# p8_led_matrix.net
KiCad netlist of a schematic drawn in Altium Designer
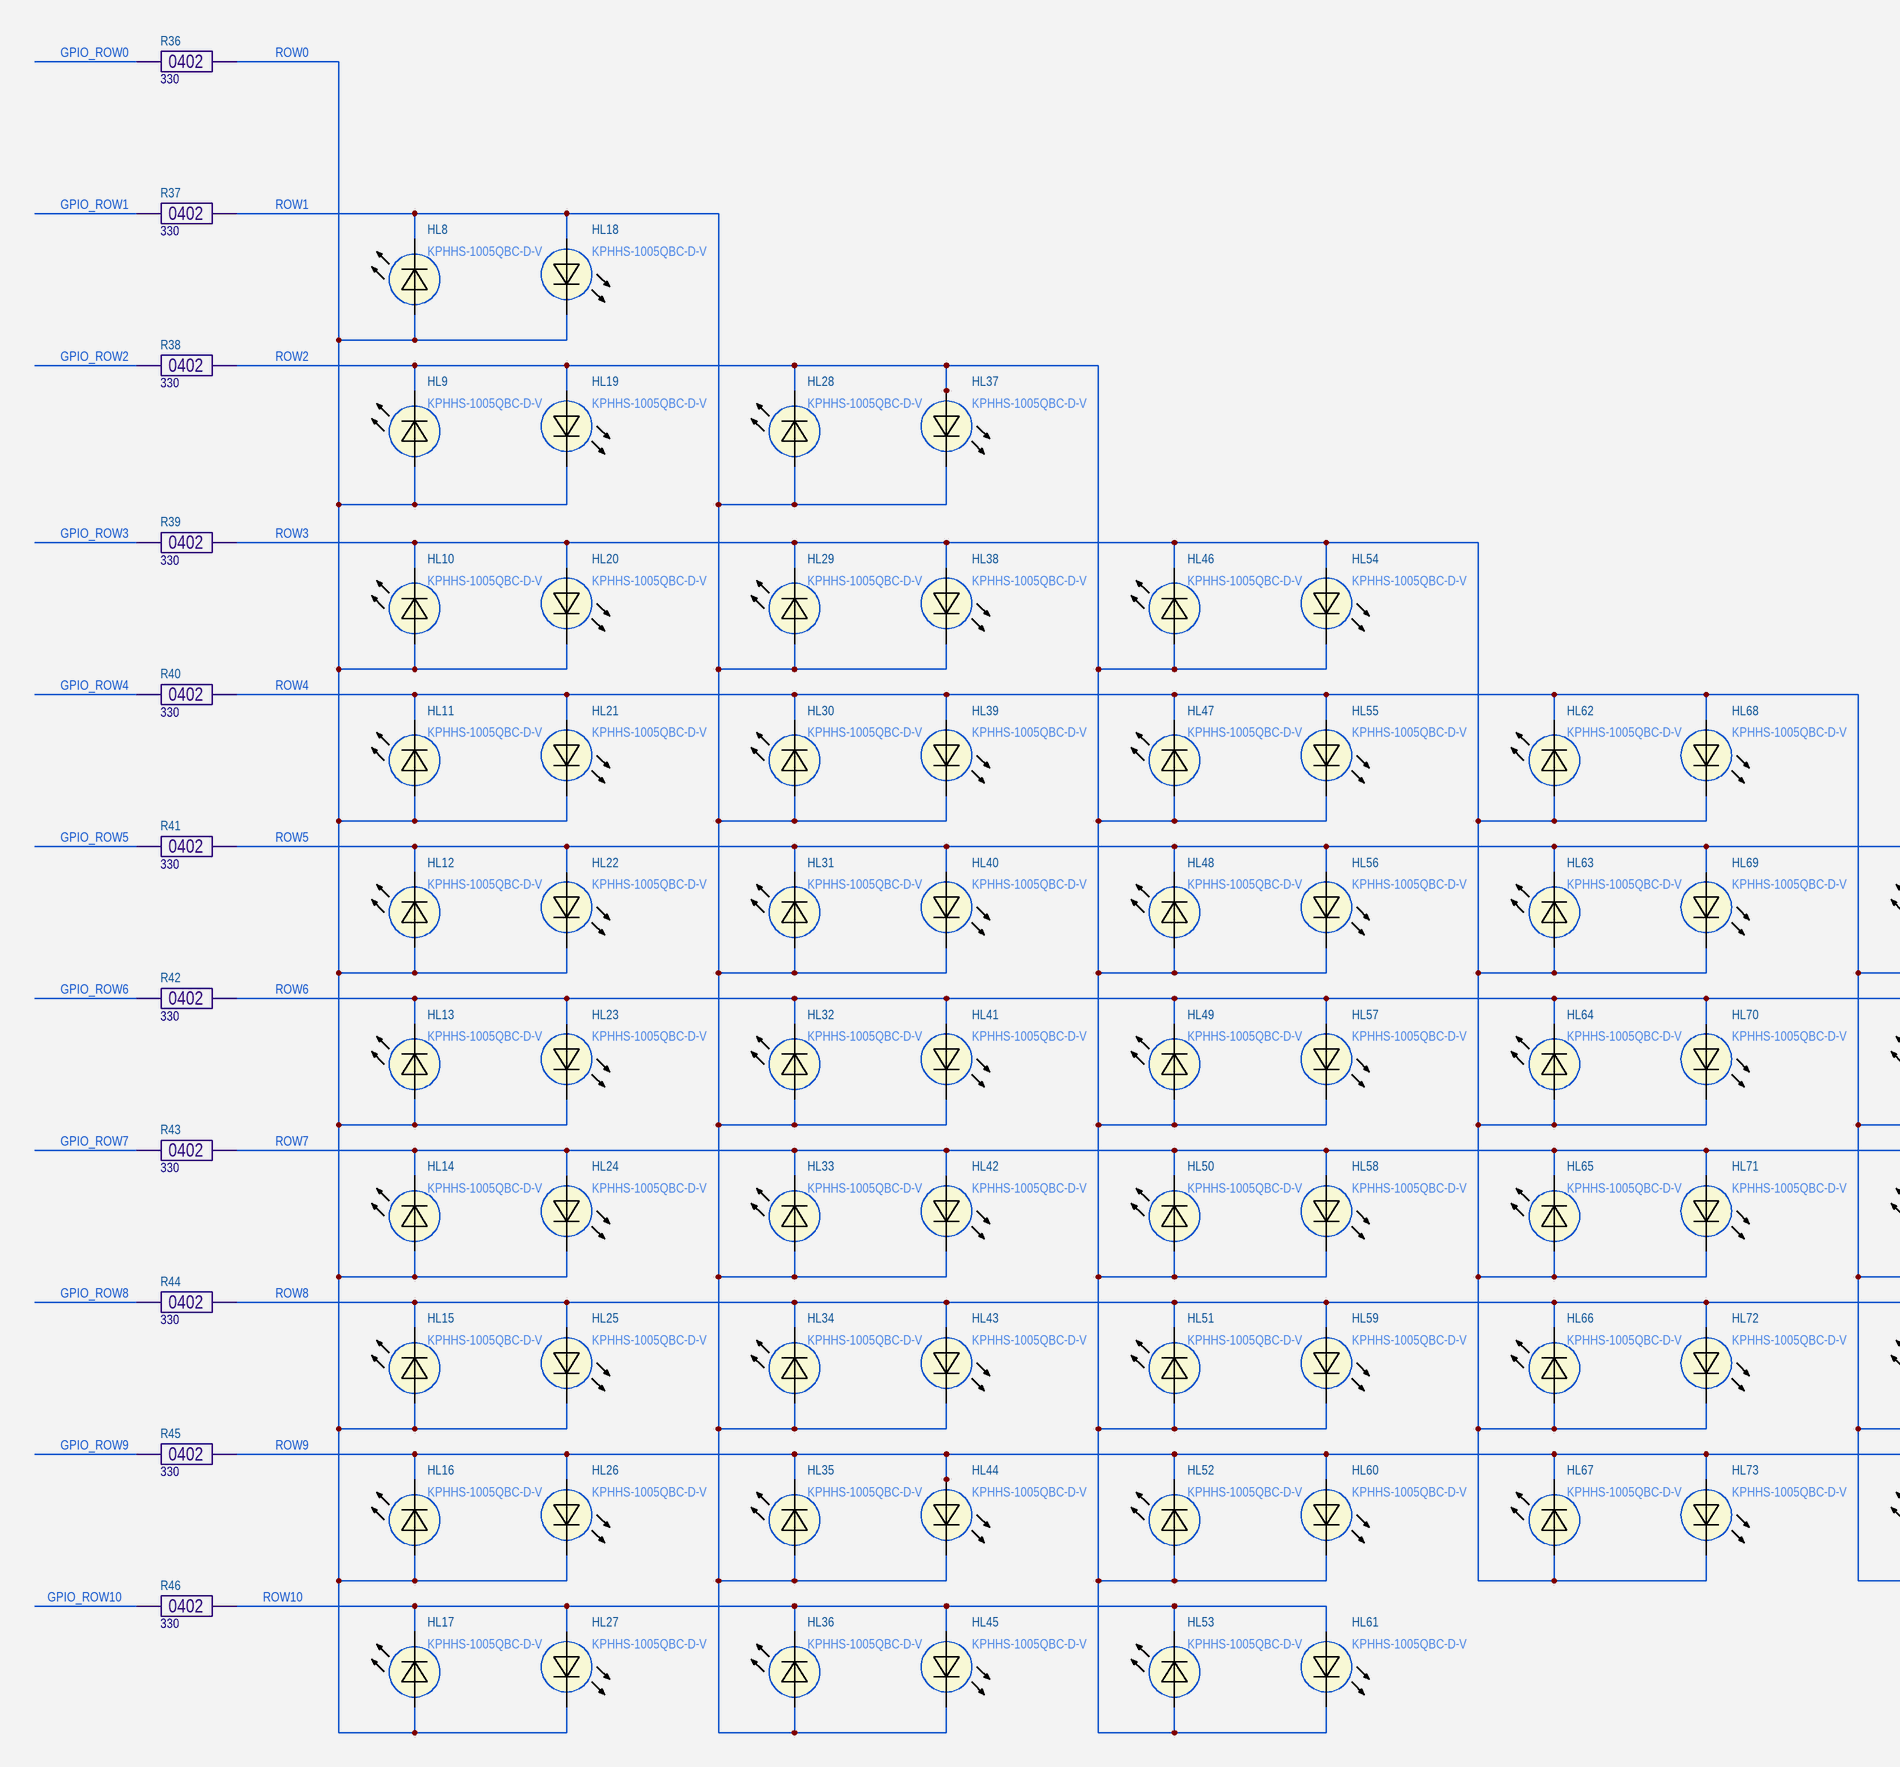
[diagram p0: p8_led_matrix.SchDoc, left]
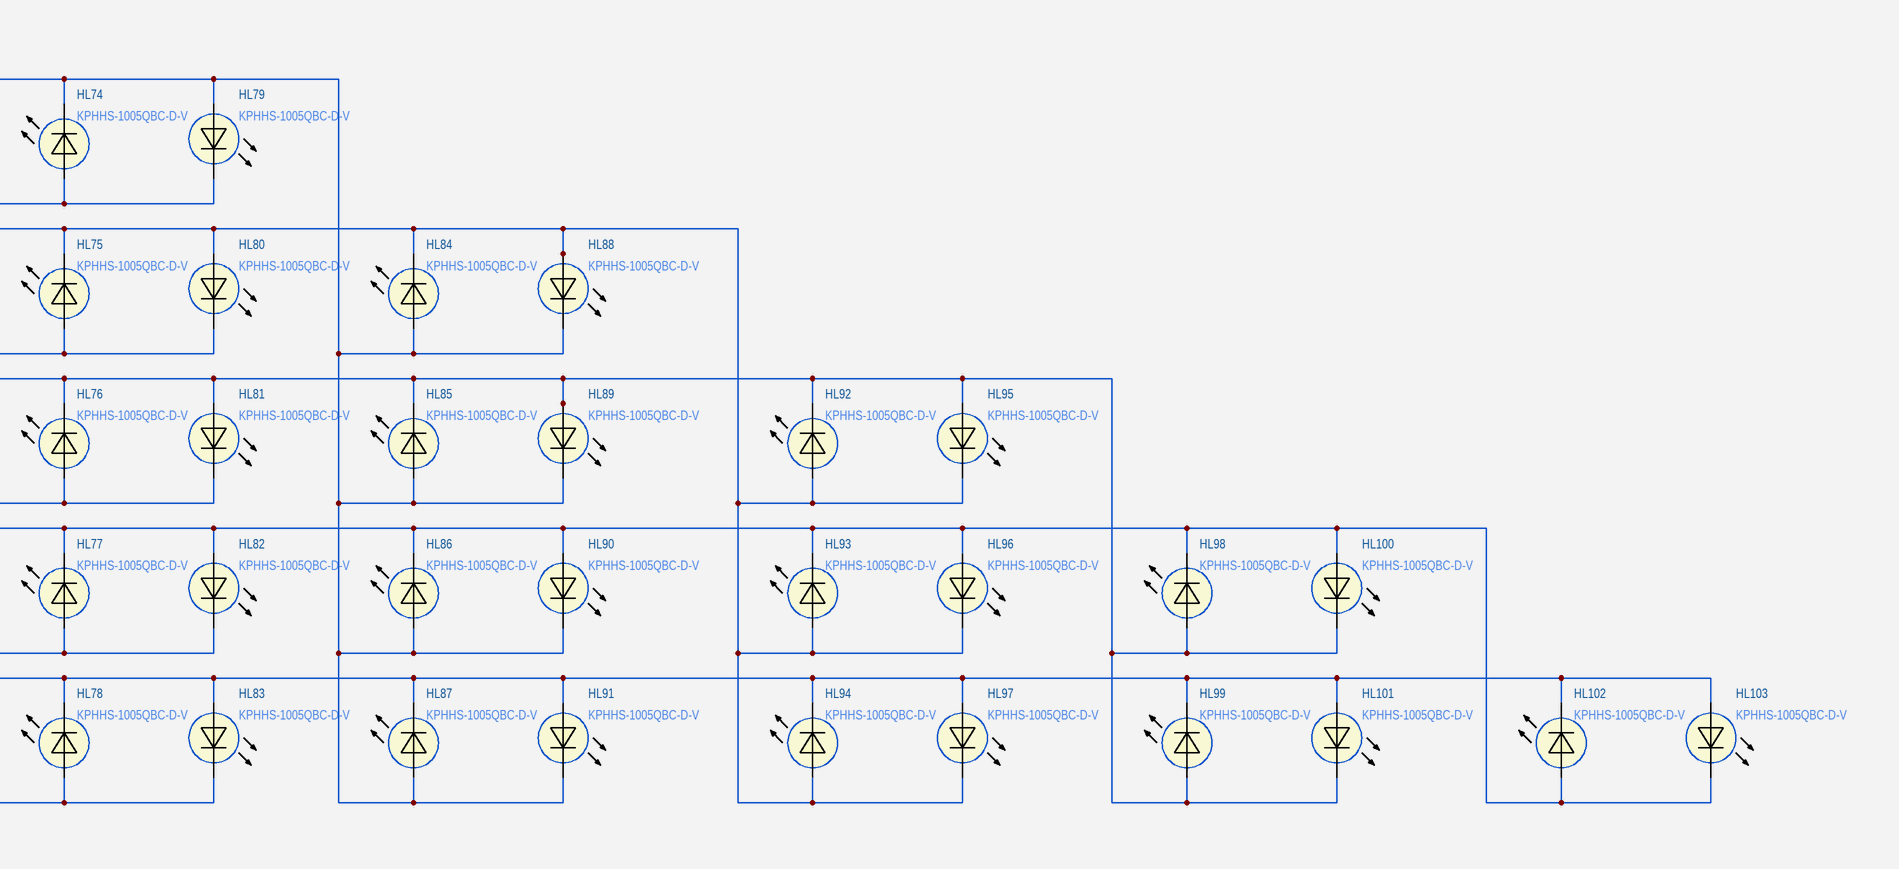
[diagram p1: p8_led_matrix.SchDoc, right]

(export (version "E")
  (design (tool "Eeschema 10.0.6"))
  (components
    (comp (ref "HL8")
      (value "KPHHS-1005QBC-D-V")
      (footprint "PcbLib_Others:LED0402B")
      (description "Blue led (package case 0402)")
      (fields (field (name "MANUFACTURER") "Kingbright Company LLC."))
      (libsource (lib "Schlib_Kingbright") (part "KPHHS-1005QBC-D-V"))
    )
    (comp (ref "HL9")
      (value "KPHHS-1005QBC-D-V")
      (footprint "PcbLib_Others:LED0402B")
      (description "Blue led (package case 0402)")
      (fields (field (name "MANUFACTURER") "Kingbright Company LLC."))
      (libsource (lib "Schlib_Kingbright") (part "KPHHS-1005QBC-D-V"))
    )
    (comp (ref "HL10")
      (value "KPHHS-1005QBC-D-V")
      (footprint "PcbLib_Others:LED0402B")
      (description "Blue led (package case 0402)")
      (fields (field (name "MANUFACTURER") "Kingbright Company LLC."))
      (libsource (lib "Schlib_Kingbright") (part "KPHHS-1005QBC-D-V"))
    )
    (comp (ref "HL11")
      (value "KPHHS-1005QBC-D-V")
      (footprint "PcbLib_Others:LED0402B")
      (description "Blue led (package case 0402)")
      (fields (field (name "MANUFACTURER") "Kingbright Company LLC."))
      (libsource (lib "Schlib_Kingbright") (part "KPHHS-1005QBC-D-V"))
    )
    (comp (ref "HL12")
      (value "KPHHS-1005QBC-D-V")
      (footprint "PcbLib_Others:LED0402B")
      (description "Blue led (package case 0402)")
      (fields (field (name "MANUFACTURER") "Kingbright Company LLC."))
      (libsource (lib "Schlib_Kingbright") (part "KPHHS-1005QBC-D-V"))
    )
    (comp (ref "HL13")
      (value "KPHHS-1005QBC-D-V")
      (footprint "PcbLib_Others:LED0402B")
      (description "Blue led (package case 0402)")
      (fields (field (name "MANUFACTURER") "Kingbright Company LLC."))
      (libsource (lib "Schlib_Kingbright") (part "KPHHS-1005QBC-D-V"))
    )
    (comp (ref "HL14")
      (value "KPHHS-1005QBC-D-V")
      (footprint "PcbLib_Others:LED0402B")
      (description "Blue led (package case 0402)")
      (fields (field (name "MANUFACTURER") "Kingbright Company LLC."))
      (libsource (lib "Schlib_Kingbright") (part "KPHHS-1005QBC-D-V"))
    )
    (comp (ref "HL15")
      (value "KPHHS-1005QBC-D-V")
      (footprint "PcbLib_Others:LED0402B")
      (description "Blue led (package case 0402)")
      (fields (field (name "MANUFACTURER") "Kingbright Company LLC."))
      (libsource (lib "Schlib_Kingbright") (part "KPHHS-1005QBC-D-V"))
    )
    (comp (ref "HL16")
      (value "KPHHS-1005QBC-D-V")
      (footprint "PcbLib_Others:LED0402B")
      (description "Blue led (package case 0402)")
      (fields (field (name "MANUFACTURER") "Kingbright Company LLC."))
      (libsource (lib "Schlib_Kingbright") (part "KPHHS-1005QBC-D-V"))
    )
    (comp (ref "HL17")
      (value "KPHHS-1005QBC-D-V")
      (footprint "PcbLib_Others:LED0402B")
      (description "Blue led (package case 0402)")
      (fields (field (name "MANUFACTURER") "Kingbright Company LLC."))
      (libsource (lib "Schlib_Kingbright") (part "KPHHS-1005QBC-D-V"))
    )
    (comp (ref "HL18")
      (value "KPHHS-1005QBC-D-V")
      (footprint "PcbLib_Others:LED0402B")
      (description "Blue led (package case 0402)")
      (fields (field (name "MANUFACTURER") "Kingbright Company LLC."))
      (libsource (lib "Schlib_Kingbright") (part "KPHHS-1005QBC-D-V"))
    )
    (comp (ref "HL19")
      (value "KPHHS-1005QBC-D-V")
      (footprint "PcbLib_Others:LED0402B")
      (description "Blue led (package case 0402)")
      (fields (field (name "MANUFACTURER") "Kingbright Company LLC."))
      (libsource (lib "Schlib_Kingbright") (part "KPHHS-1005QBC-D-V"))
    )
    (comp (ref "HL20")
      (value "KPHHS-1005QBC-D-V")
      (footprint "PcbLib_Others:LED0402B")
      (description "Blue led (package case 0402)")
      (fields (field (name "MANUFACTURER") "Kingbright Company LLC."))
      (libsource (lib "Schlib_Kingbright") (part "KPHHS-1005QBC-D-V"))
    )
    (comp (ref "HL21")
      (value "KPHHS-1005QBC-D-V")
      (footprint "PcbLib_Others:LED0402B")
      (description "Blue led (package case 0402)")
      (fields (field (name "MANUFACTURER") "Kingbright Company LLC."))
      (libsource (lib "Schlib_Kingbright") (part "KPHHS-1005QBC-D-V"))
    )
    (comp (ref "HL22")
      (value "KPHHS-1005QBC-D-V")
      (footprint "PcbLib_Others:LED0402B")
      (description "Blue led (package case 0402)")
      (fields (field (name "MANUFACTURER") "Kingbright Company LLC."))
      (libsource (lib "Schlib_Kingbright") (part "KPHHS-1005QBC-D-V"))
    )
    (comp (ref "HL23")
      (value "KPHHS-1005QBC-D-V")
      (footprint "PcbLib_Others:LED0402B")
      (description "Blue led (package case 0402)")
      (fields (field (name "MANUFACTURER") "Kingbright Company LLC."))
      (libsource (lib "Schlib_Kingbright") (part "KPHHS-1005QBC-D-V"))
    )
    (comp (ref "HL24")
      (value "KPHHS-1005QBC-D-V")
      (footprint "PcbLib_Others:LED0402B")
      (description "Blue led (package case 0402)")
      (fields (field (name "MANUFACTURER") "Kingbright Company LLC."))
      (libsource (lib "Schlib_Kingbright") (part "KPHHS-1005QBC-D-V"))
    )
    (comp (ref "HL25")
      (value "KPHHS-1005QBC-D-V")
      (footprint "PcbLib_Others:LED0402B")
      (description "Blue led (package case 0402)")
      (fields (field (name "MANUFACTURER") "Kingbright Company LLC."))
      (libsource (lib "Schlib_Kingbright") (part "KPHHS-1005QBC-D-V"))
    )
    (comp (ref "HL26")
      (value "KPHHS-1005QBC-D-V")
      (footprint "PcbLib_Others:LED0402B")
      (description "Blue led (package case 0402)")
      (fields (field (name "MANUFACTURER") "Kingbright Company LLC."))
      (libsource (lib "Schlib_Kingbright") (part "KPHHS-1005QBC-D-V"))
    )
    (comp (ref "HL27")
      (value "KPHHS-1005QBC-D-V")
      (footprint "PcbLib_Others:LED0402B")
      (description "Blue led (package case 0402)")
      (fields (field (name "MANUFACTURER") "Kingbright Company LLC."))
      (libsource (lib "Schlib_Kingbright") (part "KPHHS-1005QBC-D-V"))
    )
    (comp (ref "HL28")
      (value "KPHHS-1005QBC-D-V")
      (footprint "PcbLib_Others:LED0402B")
      (description "Blue led (package case 0402)")
      (fields (field (name "MANUFACTURER") "Kingbright Company LLC."))
      (libsource (lib "Schlib_Kingbright") (part "KPHHS-1005QBC-D-V"))
    )
    (comp (ref "HL29")
      (value "KPHHS-1005QBC-D-V")
      (footprint "PcbLib_Others:LED0402B")
      (description "Blue led (package case 0402)")
      (fields (field (name "MANUFACTURER") "Kingbright Company LLC."))
      (libsource (lib "Schlib_Kingbright") (part "KPHHS-1005QBC-D-V"))
    )
    (comp (ref "HL30")
      (value "KPHHS-1005QBC-D-V")
      (footprint "PcbLib_Others:LED0402B")
      (description "Blue led (package case 0402)")
      (fields (field (name "MANUFACTURER") "Kingbright Company LLC."))
      (libsource (lib "Schlib_Kingbright") (part "KPHHS-1005QBC-D-V"))
    )
    (comp (ref "HL31")
      (value "KPHHS-1005QBC-D-V")
      (footprint "PcbLib_Others:LED0402B")
      (description "Blue led (package case 0402)")
      (fields (field (name "MANUFACTURER") "Kingbright Company LLC."))
      (libsource (lib "Schlib_Kingbright") (part "KPHHS-1005QBC-D-V"))
    )
    (comp (ref "HL32")
      (value "KPHHS-1005QBC-D-V")
      (footprint "PcbLib_Others:LED0402B")
      (description "Blue led (package case 0402)")
      (fields (field (name "MANUFACTURER") "Kingbright Company LLC."))
      (libsource (lib "Schlib_Kingbright") (part "KPHHS-1005QBC-D-V"))
    )
    (comp (ref "HL33")
      (value "KPHHS-1005QBC-D-V")
      (footprint "PcbLib_Others:LED0402B")
      (description "Blue led (package case 0402)")
      (fields (field (name "MANUFACTURER") "Kingbright Company LLC."))
      (libsource (lib "Schlib_Kingbright") (part "KPHHS-1005QBC-D-V"))
    )
    (comp (ref "HL34")
      (value "KPHHS-1005QBC-D-V")
      (footprint "PcbLib_Others:LED0402B")
      (description "Blue led (package case 0402)")
      (fields (field (name "MANUFACTURER") "Kingbright Company LLC."))
      (libsource (lib "Schlib_Kingbright") (part "KPHHS-1005QBC-D-V"))
    )
    (comp (ref "HL35")
      (value "KPHHS-1005QBC-D-V")
      (footprint "PcbLib_Others:LED0402B")
      (description "Blue led (package case 0402)")
      (fields (field (name "MANUFACTURER") "Kingbright Company LLC."))
      (libsource (lib "Schlib_Kingbright") (part "KPHHS-1005QBC-D-V"))
    )
    (comp (ref "HL36")
      (value "KPHHS-1005QBC-D-V")
      (footprint "PcbLib_Others:LED0402B")
      (description "Blue led (package case 0402)")
      (fields (field (name "MANUFACTURER") "Kingbright Company LLC."))
      (libsource (lib "Schlib_Kingbright") (part "KPHHS-1005QBC-D-V"))
    )
    (comp (ref "HL37")
      (value "KPHHS-1005QBC-D-V")
      (footprint "PcbLib_Others:LED0402B")
      (description "Blue led (package case 0402)")
      (fields (field (name "MANUFACTURER") "Kingbright Company LLC."))
      (libsource (lib "Schlib_Kingbright") (part "KPHHS-1005QBC-D-V"))
    )
    (comp (ref "HL38")
      (value "KPHHS-1005QBC-D-V")
      (footprint "PcbLib_Others:LED0402B")
      (description "Blue led (package case 0402)")
      (fields (field (name "MANUFACTURER") "Kingbright Company LLC."))
      (libsource (lib "Schlib_Kingbright") (part "KPHHS-1005QBC-D-V"))
    )
    (comp (ref "HL39")
      (value "KPHHS-1005QBC-D-V")
      (footprint "PcbLib_Others:LED0402B")
      (description "Blue led (package case 0402)")
      (fields (field (name "MANUFACTURER") "Kingbright Company LLC."))
      (libsource (lib "Schlib_Kingbright") (part "KPHHS-1005QBC-D-V"))
    )
    (comp (ref "HL40")
      (value "KPHHS-1005QBC-D-V")
      (footprint "PcbLib_Others:LED0402B")
      (description "Blue led (package case 0402)")
      (fields (field (name "MANUFACTURER") "Kingbright Company LLC."))
      (libsource (lib "Schlib_Kingbright") (part "KPHHS-1005QBC-D-V"))
    )
    (comp (ref "HL41")
      (value "KPHHS-1005QBC-D-V")
      (footprint "PcbLib_Others:LED0402B")
      (description "Blue led (package case 0402)")
      (fields (field (name "MANUFACTURER") "Kingbright Company LLC."))
      (libsource (lib "Schlib_Kingbright") (part "KPHHS-1005QBC-D-V"))
    )
    (comp (ref "HL42")
      (value "KPHHS-1005QBC-D-V")
      (footprint "PcbLib_Others:LED0402B")
      (description "Blue led (package case 0402)")
      (fields (field (name "MANUFACTURER") "Kingbright Company LLC."))
      (libsource (lib "Schlib_Kingbright") (part "KPHHS-1005QBC-D-V"))
    )
    (comp (ref "HL43")
      (value "KPHHS-1005QBC-D-V")
      (footprint "PcbLib_Others:LED0402B")
      (description "Blue led (package case 0402)")
      (fields (field (name "MANUFACTURER") "Kingbright Company LLC."))
      (libsource (lib "Schlib_Kingbright") (part "KPHHS-1005QBC-D-V"))
    )
    (comp (ref "HL44")
      (value "KPHHS-1005QBC-D-V")
      (footprint "PcbLib_Others:LED0402B")
      (description "Blue led (package case 0402)")
      (fields (field (name "MANUFACTURER") "Kingbright Company LLC."))
      (libsource (lib "Schlib_Kingbright") (part "KPHHS-1005QBC-D-V"))
    )
    (comp (ref "HL45")
      (value "KPHHS-1005QBC-D-V")
      (footprint "PcbLib_Others:LED0402B")
      (description "Blue led (package case 0402)")
      (fields (field (name "MANUFACTURER") "Kingbright Company LLC."))
      (libsource (lib "Schlib_Kingbright") (part "KPHHS-1005QBC-D-V"))
    )
    (comp (ref "HL46")
      (value "KPHHS-1005QBC-D-V")
      (footprint "PcbLib_Others:LED0402B")
      (description "Blue led (package case 0402)")
      (fields (field (name "MANUFACTURER") "Kingbright Company LLC."))
      (libsource (lib "Schlib_Kingbright") (part "KPHHS-1005QBC-D-V"))
    )
    (comp (ref "HL47")
      (value "KPHHS-1005QBC-D-V")
      (footprint "PcbLib_Others:LED0402B")
      (description "Blue led (package case 0402)")
      (fields (field (name "MANUFACTURER") "Kingbright Company LLC."))
      (libsource (lib "Schlib_Kingbright") (part "KPHHS-1005QBC-D-V"))
    )
    (comp (ref "HL48")
      (value "KPHHS-1005QBC-D-V")
      (footprint "PcbLib_Others:LED0402B")
      (description "Blue led (package case 0402)")
      (fields (field (name "MANUFACTURER") "Kingbright Company LLC."))
      (libsource (lib "Schlib_Kingbright") (part "KPHHS-1005QBC-D-V"))
    )
    (comp (ref "HL49")
      (value "KPHHS-1005QBC-D-V")
      (footprint "PcbLib_Others:LED0402B")
      (description "Blue led (package case 0402)")
      (fields (field (name "MANUFACTURER") "Kingbright Company LLC."))
      (libsource (lib "Schlib_Kingbright") (part "KPHHS-1005QBC-D-V"))
    )
    (comp (ref "HL50")
      (value "KPHHS-1005QBC-D-V")
      (footprint "PcbLib_Others:LED0402B")
      (description "Blue led (package case 0402)")
      (fields (field (name "MANUFACTURER") "Kingbright Company LLC."))
      (libsource (lib "Schlib_Kingbright") (part "KPHHS-1005QBC-D-V"))
    )
    (comp (ref "HL51")
      (value "KPHHS-1005QBC-D-V")
      (footprint "PcbLib_Others:LED0402B")
      (description "Blue led (package case 0402)")
      (fields (field (name "MANUFACTURER") "Kingbright Company LLC."))
      (libsource (lib "Schlib_Kingbright") (part "KPHHS-1005QBC-D-V"))
    )
    (comp (ref "HL52")
      (value "KPHHS-1005QBC-D-V")
      (footprint "PcbLib_Others:LED0402B")
      (description "Blue led (package case 0402)")
      (fields (field (name "MANUFACTURER") "Kingbright Company LLC."))
      (libsource (lib "Schlib_Kingbright") (part "KPHHS-1005QBC-D-V"))
    )
    (comp (ref "HL53")
      (value "KPHHS-1005QBC-D-V")
      (footprint "PcbLib_Others:LED0402B")
      (description "Blue led (package case 0402)")
      (fields (field (name "MANUFACTURER") "Kingbright Company LLC."))
      (libsource (lib "Schlib_Kingbright") (part "KPHHS-1005QBC-D-V"))
    )
    (comp (ref "HL54")
      (value "KPHHS-1005QBC-D-V")
      (footprint "PcbLib_Others:LED0402B")
      (description "Blue led (package case 0402)")
      (fields (field (name "MANUFACTURER") "Kingbright Company LLC."))
      (libsource (lib "Schlib_Kingbright") (part "KPHHS-1005QBC-D-V"))
    )
    (comp (ref "HL55")
      (value "KPHHS-1005QBC-D-V")
      (footprint "PcbLib_Others:LED0402B")
      (description "Blue led (package case 0402)")
      (fields (field (name "MANUFACTURER") "Kingbright Company LLC."))
      (libsource (lib "Schlib_Kingbright") (part "KPHHS-1005QBC-D-V"))
    )
    (comp (ref "HL56")
      (value "KPHHS-1005QBC-D-V")
      (footprint "PcbLib_Others:LED0402B")
      (description "Blue led (package case 0402)")
      (fields (field (name "MANUFACTURER") "Kingbright Company LLC."))
      (libsource (lib "Schlib_Kingbright") (part "KPHHS-1005QBC-D-V"))
    )
    (comp (ref "HL57")
      (value "KPHHS-1005QBC-D-V")
      (footprint "PcbLib_Others:LED0402B")
      (description "Blue led (package case 0402)")
      (fields (field (name "MANUFACTURER") "Kingbright Company LLC."))
      (libsource (lib "Schlib_Kingbright") (part "KPHHS-1005QBC-D-V"))
    )
    (comp (ref "HL58")
      (value "KPHHS-1005QBC-D-V")
      (footprint "PcbLib_Others:LED0402B")
      (description "Blue led (package case 0402)")
      (fields (field (name "MANUFACTURER") "Kingbright Company LLC."))
      (libsource (lib "Schlib_Kingbright") (part "KPHHS-1005QBC-D-V"))
    )
    (comp (ref "HL59")
      (value "KPHHS-1005QBC-D-V")
      (footprint "PcbLib_Others:LED0402B")
      (description "Blue led (package case 0402)")
      (fields (field (name "MANUFACTURER") "Kingbright Company LLC."))
      (libsource (lib "Schlib_Kingbright") (part "KPHHS-1005QBC-D-V"))
    )
    (comp (ref "HL60")
      (value "KPHHS-1005QBC-D-V")
      (footprint "PcbLib_Others:LED0402B")
      (description "Blue led (package case 0402)")
      (fields (field (name "MANUFACTURER") "Kingbright Company LLC."))
      (libsource (lib "Schlib_Kingbright") (part "KPHHS-1005QBC-D-V"))
    )
    (comp (ref "HL61")
      (value "KPHHS-1005QBC-D-V")
      (footprint "PcbLib_Others:LED0402B")
      (description "Blue led (package case 0402)")
      (fields (field (name "MANUFACTURER") "Kingbright Company LLC."))
      (libsource (lib "Schlib_Kingbright") (part "KPHHS-1005QBC-D-V"))
    )
    (comp (ref "HL62")
      (value "KPHHS-1005QBC-D-V")
      (footprint "PcbLib_Others:LED0402B")
      (description "Blue led (package case 0402)")
      (fields (field (name "MANUFACTURER") "Kingbright Company LLC."))
      (libsource (lib "Schlib_Kingbright") (part "KPHHS-1005QBC-D-V"))
    )
    (comp (ref "HL63")
      (value "KPHHS-1005QBC-D-V")
      (footprint "PcbLib_Others:LED0402B")
      (description "Blue led (package case 0402)")
      (fields (field (name "MANUFACTURER") "Kingbright Company LLC."))
      (libsource (lib "Schlib_Kingbright") (part "KPHHS-1005QBC-D-V"))
    )
    (comp (ref "HL64")
      (value "KPHHS-1005QBC-D-V")
      (footprint "PcbLib_Others:LED0402B")
      (description "Blue led (package case 0402)")
      (fields (field (name "MANUFACTURER") "Kingbright Company LLC."))
      (libsource (lib "Schlib_Kingbright") (part "KPHHS-1005QBC-D-V"))
    )
    (comp (ref "HL65")
      (value "KPHHS-1005QBC-D-V")
      (footprint "PcbLib_Others:LED0402B")
      (description "Blue led (package case 0402)")
      (fields (field (name "MANUFACTURER") "Kingbright Company LLC."))
      (libsource (lib "Schlib_Kingbright") (part "KPHHS-1005QBC-D-V"))
    )
    (comp (ref "HL66")
      (value "KPHHS-1005QBC-D-V")
      (footprint "PcbLib_Others:LED0402B")
      (description "Blue led (package case 0402)")
      (fields (field (name "MANUFACTURER") "Kingbright Company LLC."))
      (libsource (lib "Schlib_Kingbright") (part "KPHHS-1005QBC-D-V"))
    )
    (comp (ref "HL67")
      (value "KPHHS-1005QBC-D-V")
      (footprint "PcbLib_Others:LED0402B")
      (description "Blue led (package case 0402)")
      (fields (field (name "MANUFACTURER") "Kingbright Company LLC."))
      (libsource (lib "Schlib_Kingbright") (part "KPHHS-1005QBC-D-V"))
    )
    (comp (ref "HL68")
      (value "KPHHS-1005QBC-D-V")
      (footprint "PcbLib_Others:LED0402B")
      (description "Blue led (package case 0402)")
      (fields (field (name "MANUFACTURER") "Kingbright Company LLC."))
      (libsource (lib "Schlib_Kingbright") (part "KPHHS-1005QBC-D-V"))
    )
    (comp (ref "HL69")
      (value "KPHHS-1005QBC-D-V")
      (footprint "PcbLib_Others:LED0402B")
      (description "Blue led (package case 0402)")
      (fields (field (name "MANUFACTURER") "Kingbright Company LLC."))
      (libsource (lib "Schlib_Kingbright") (part "KPHHS-1005QBC-D-V"))
    )
    (comp (ref "HL70")
      (value "KPHHS-1005QBC-D-V")
      (footprint "PcbLib_Others:LED0402B")
      (description "Blue led (package case 0402)")
      (fields (field (name "MANUFACTURER") "Kingbright Company LLC."))
      (libsource (lib "Schlib_Kingbright") (part "KPHHS-1005QBC-D-V"))
    )
    (comp (ref "HL71")
      (value "KPHHS-1005QBC-D-V")
      (footprint "PcbLib_Others:LED0402B")
      (description "Blue led (package case 0402)")
      (fields (field (name "MANUFACTURER") "Kingbright Company LLC."))
      (libsource (lib "Schlib_Kingbright") (part "KPHHS-1005QBC-D-V"))
    )
    (comp (ref "HL72")
      (value "KPHHS-1005QBC-D-V")
      (footprint "PcbLib_Others:LED0402B")
      (description "Blue led (package case 0402)")
      (fields (field (name "MANUFACTURER") "Kingbright Company LLC."))
      (libsource (lib "Schlib_Kingbright") (part "KPHHS-1005QBC-D-V"))
    )
    (comp (ref "HL73")
      (value "KPHHS-1005QBC-D-V")
      (footprint "PcbLib_Others:LED0402B")
      (description "Blue led (package case 0402)")
      (fields (field (name "MANUFACTURER") "Kingbright Company LLC."))
      (libsource (lib "Schlib_Kingbright") (part "KPHHS-1005QBC-D-V"))
    )
    (comp (ref "HL74")
      (value "KPHHS-1005QBC-D-V")
      (footprint "PcbLib_Others:LED0402B")
      (description "Blue led (package case 0402)")
      (fields (field (name "MANUFACTURER") "Kingbright Company LLC."))
      (libsource (lib "Schlib_Kingbright") (part "KPHHS-1005QBC-D-V"))
    )
    (comp (ref "HL75")
      (value "KPHHS-1005QBC-D-V")
      (footprint "PcbLib_Others:LED0402B")
      (description "Blue led (package case 0402)")
      (fields (field (name "MANUFACTURER") "Kingbright Company LLC."))
      (libsource (lib "Schlib_Kingbright") (part "KPHHS-1005QBC-D-V"))
    )
    (comp (ref "HL76")
      (value "KPHHS-1005QBC-D-V")
      (footprint "PcbLib_Others:LED0402B")
      (description "Blue led (package case 0402)")
      (fields (field (name "MANUFACTURER") "Kingbright Company LLC."))
      (libsource (lib "Schlib_Kingbright") (part "KPHHS-1005QBC-D-V"))
    )
    (comp (ref "HL77")
      (value "KPHHS-1005QBC-D-V")
      (footprint "PcbLib_Others:LED0402B")
      (description "Blue led (package case 0402)")
      (fields (field (name "MANUFACTURER") "Kingbright Company LLC."))
      (libsource (lib "Schlib_Kingbright") (part "KPHHS-1005QBC-D-V"))
    )
    (comp (ref "HL78")
      (value "KPHHS-1005QBC-D-V")
      (footprint "PcbLib_Others:LED0402B")
      (description "Blue led (package case 0402)")
      (fields (field (name "MANUFACTURER") "Kingbright Company LLC."))
      (libsource (lib "Schlib_Kingbright") (part "KPHHS-1005QBC-D-V"))
    )
    (comp (ref "HL79")
      (value "KPHHS-1005QBC-D-V")
      (footprint "PcbLib_Others:LED0402B")
      (description "Blue led (package case 0402)")
      (fields (field (name "MANUFACTURER") "Kingbright Company LLC."))
      (libsource (lib "Schlib_Kingbright") (part "KPHHS-1005QBC-D-V"))
    )
    (comp (ref "HL80")
      (value "KPHHS-1005QBC-D-V")
      (footprint "PcbLib_Others:LED0402B")
      (description "Blue led (package case 0402)")
      (fields (field (name "MANUFACTURER") "Kingbright Company LLC."))
      (libsource (lib "Schlib_Kingbright") (part "KPHHS-1005QBC-D-V"))
    )
    (comp (ref "HL81")
      (value "KPHHS-1005QBC-D-V")
      (footprint "PcbLib_Others:LED0402B")
      (description "Blue led (package case 0402)")
      (fields (field (name "MANUFACTURER") "Kingbright Company LLC."))
      (libsource (lib "Schlib_Kingbright") (part "KPHHS-1005QBC-D-V"))
    )
    (comp (ref "HL82")
      (value "KPHHS-1005QBC-D-V")
      (footprint "PcbLib_Others:LED0402B")
      (description "Blue led (package case 0402)")
      (fields (field (name "MANUFACTURER") "Kingbright Company LLC."))
      (libsource (lib "Schlib_Kingbright") (part "KPHHS-1005QBC-D-V"))
    )
    (comp (ref "HL83")
      (value "KPHHS-1005QBC-D-V")
      (footprint "PcbLib_Others:LED0402B")
      (description "Blue led (package case 0402)")
      (fields (field (name "MANUFACTURER") "Kingbright Company LLC."))
      (libsource (lib "Schlib_Kingbright") (part "KPHHS-1005QBC-D-V"))
    )
    (comp (ref "HL84")
      (value "KPHHS-1005QBC-D-V")
      (footprint "PcbLib_Others:LED0402B")
      (description "Blue led (package case 0402)")
      (fields (field (name "MANUFACTURER") "Kingbright Company LLC."))
      (libsource (lib "Schlib_Kingbright") (part "KPHHS-1005QBC-D-V"))
    )
    (comp (ref "HL85")
      (value "KPHHS-1005QBC-D-V")
      (footprint "PcbLib_Others:LED0402B")
      (description "Blue led (package case 0402)")
      (fields (field (name "MANUFACTURER") "Kingbright Company LLC."))
      (libsource (lib "Schlib_Kingbright") (part "KPHHS-1005QBC-D-V"))
    )
    (comp (ref "HL86")
      (value "KPHHS-1005QBC-D-V")
      (footprint "PcbLib_Others:LED0402B")
      (description "Blue led (package case 0402)")
      (fields (field (name "MANUFACTURER") "Kingbright Company LLC."))
      (libsource (lib "Schlib_Kingbright") (part "KPHHS-1005QBC-D-V"))
    )
    (comp (ref "HL87")
      (value "KPHHS-1005QBC-D-V")
      (footprint "PcbLib_Others:LED0402B")
      (description "Blue led (package case 0402)")
      (fields (field (name "MANUFACTURER") "Kingbright Company LLC."))
      (libsource (lib "Schlib_Kingbright") (part "KPHHS-1005QBC-D-V"))
    )
    (comp (ref "HL88")
      (value "KPHHS-1005QBC-D-V")
      (footprint "PcbLib_Others:LED0402B")
      (description "Blue led (package case 0402)")
      (fields (field (name "MANUFACTURER") "Kingbright Company LLC."))
      (libsource (lib "Schlib_Kingbright") (part "KPHHS-1005QBC-D-V"))
    )
    (comp (ref "HL89")
      (value "KPHHS-1005QBC-D-V")
      (footprint "PcbLib_Others:LED0402B")
      (description "Blue led (package case 0402)")
      (fields (field (name "MANUFACTURER") "Kingbright Company LLC."))
      (libsource (lib "Schlib_Kingbright") (part "KPHHS-1005QBC-D-V"))
    )
    (comp (ref "HL90")
      (value "KPHHS-1005QBC-D-V")
      (footprint "PcbLib_Others:LED0402B")
      (description "Blue led (package case 0402)")
      (fields (field (name "MANUFACTURER") "Kingbright Company LLC."))
      (libsource (lib "Schlib_Kingbright") (part "KPHHS-1005QBC-D-V"))
    )
    (comp (ref "HL91")
      (value "KPHHS-1005QBC-D-V")
      (footprint "PcbLib_Others:LED0402B")
      (description "Blue led (package case 0402)")
      (fields (field (name "MANUFACTURER") "Kingbright Company LLC."))
      (libsource (lib "Schlib_Kingbright") (part "KPHHS-1005QBC-D-V"))
    )
    (comp (ref "HL92")
      (value "KPHHS-1005QBC-D-V")
      (footprint "PcbLib_Others:LED0402B")
      (description "Blue led (package case 0402)")
      (fields (field (name "MANUFACTURER") "Kingbright Company LLC."))
      (libsource (lib "Schlib_Kingbright") (part "KPHHS-1005QBC-D-V"))
    )
    (comp (ref "HL93")
      (value "KPHHS-1005QBC-D-V")
      (footprint "PcbLib_Others:LED0402B")
      (description "Blue led (package case 0402)")
      (fields (field (name "MANUFACTURER") "Kingbright Company LLC."))
      (libsource (lib "Schlib_Kingbright") (part "KPHHS-1005QBC-D-V"))
    )
    (comp (ref "HL94")
      (value "KPHHS-1005QBC-D-V")
      (footprint "PcbLib_Others:LED0402B")
      (description "Blue led (package case 0402)")
      (fields (field (name "MANUFACTURER") "Kingbright Company LLC."))
      (libsource (lib "Schlib_Kingbright") (part "KPHHS-1005QBC-D-V"))
    )
    (comp (ref "HL95")
      (value "KPHHS-1005QBC-D-V")
      (footprint "PcbLib_Others:LED0402B")
      (description "Blue led (package case 0402)")
      (fields (field (name "MANUFACTURER") "Kingbright Company LLC."))
      (libsource (lib "Schlib_Kingbright") (part "KPHHS-1005QBC-D-V"))
    )
    (comp (ref "HL96")
      (value "KPHHS-1005QBC-D-V")
      (footprint "PcbLib_Others:LED0402B")
      (description "Blue led (package case 0402)")
      (fields (field (name "MANUFACTURER") "Kingbright Company LLC."))
      (libsource (lib "Schlib_Kingbright") (part "KPHHS-1005QBC-D-V"))
    )
    (comp (ref "HL97")
      (value "KPHHS-1005QBC-D-V")
      (footprint "PcbLib_Others:LED0402B")
      (description "Blue led (package case 0402)")
      (fields (field (name "MANUFACTURER") "Kingbright Company LLC."))
      (libsource (lib "Schlib_Kingbright") (part "KPHHS-1005QBC-D-V"))
    )
    (comp (ref "HL98")
      (value "KPHHS-1005QBC-D-V")
      (footprint "PcbLib_Others:LED0402B")
      (description "Blue led (package case 0402)")
      (fields (field (name "MANUFACTURER") "Kingbright Company LLC."))
      (libsource (lib "Schlib_Kingbright") (part "KPHHS-1005QBC-D-V"))
    )
    (comp (ref "HL99")
      (value "KPHHS-1005QBC-D-V")
      (footprint "PcbLib_Others:LED0402B")
      (description "Blue led (package case 0402)")
      (fields (field (name "MANUFACTURER") "Kingbright Company LLC."))
      (libsource (lib "Schlib_Kingbright") (part "KPHHS-1005QBC-D-V"))
    )
    (comp (ref "HL100")
      (value "KPHHS-1005QBC-D-V")
      (footprint "PcbLib_Others:LED0402B")
      (description "Blue led (package case 0402)")
      (fields (field (name "MANUFACTURER") "Kingbright Company LLC."))
      (libsource (lib "Schlib_Kingbright") (part "KPHHS-1005QBC-D-V"))
    )
    (comp (ref "HL101")
      (value "KPHHS-1005QBC-D-V")
      (footprint "PcbLib_Others:LED0402B")
      (description "Blue led (package case 0402)")
      (fields (field (name "MANUFACTURER") "Kingbright Company LLC."))
      (libsource (lib "Schlib_Kingbright") (part "KPHHS-1005QBC-D-V"))
    )
    (comp (ref "HL102")
      (value "KPHHS-1005QBC-D-V")
      (footprint "PcbLib_Others:LED0402B")
      (description "Blue led (package case 0402)")
      (fields (field (name "MANUFACTURER") "Kingbright Company LLC."))
      (libsource (lib "Schlib_Kingbright") (part "KPHHS-1005QBC-D-V"))
    )
    (comp (ref "HL103")
      (value "KPHHS-1005QBC-D-V")
      (footprint "PcbLib_Others:LED0402B")
      (description "Blue led (package case 0402)")
      (fields (field (name "MANUFACTURER") "Kingbright Company LLC."))
      (libsource (lib "Schlib_Kingbright") (part "KPHHS-1005QBC-D-V"))
    )
    (comp (ref "R36")
      (value "330")
      (footprint "PcbLib_RC:RES0402B")
      (description "Resistor 0402 package case")
      (fields
        (field (name "TOLERANCE") "± 1 %")
        (field (name "PART NUMBER") "RC0402FR-07330RL")
        (field (name "PACKAGE") "0402")
      )
      (libsource (lib "Schlib_RC") (part "R0402"))
    )
    (comp (ref "R37")
      (value "330")
      (footprint "PcbLib_RC:RES0402B")
      (description "Resistor 0402 package case")
      (fields
        (field (name "TOLERANCE") "± 1 %")
        (field (name "PART NUMBER") "RC0402FR-07330RL")
        (field (name "PACKAGE") "0402")
      )
      (libsource (lib "Schlib_RC") (part "R0402"))
    )
    (comp (ref "R38")
      (value "330")
      (footprint "PcbLib_RC:RES0402B")
      (description "Resistor 0402 package case")
      (fields
        (field (name "TOLERANCE") "± 1 %")
        (field (name "PART NUMBER") "RC0402FR-07330RL")
        (field (name "PACKAGE") "0402")
      )
      (libsource (lib "Schlib_RC") (part "R0402"))
    )
    (comp (ref "R39")
      (value "330")
      (footprint "PcbLib_RC:RES0402B")
      (description "Resistor 0402 package case")
      (fields
        (field (name "TOLERANCE") "± 1 %")
        (field (name "PART NUMBER") "RC0402FR-07330RL")
        (field (name "PACKAGE") "0402")
      )
      (libsource (lib "Schlib_RC") (part "R0402"))
    )
    (comp (ref "R40")
      (value "330")
      (footprint "PcbLib_RC:RES0402B")
      (description "Resistor 0402 package case")
      (fields
        (field (name "TOLERANCE") "± 1 %")
        (field (name "PART NUMBER") "RC0402FR-07330RL")
        (field (name "PACKAGE") "0402")
      )
      (libsource (lib "Schlib_RC") (part "R0402"))
    )
    (comp (ref "R41")
      (value "330")
      (footprint "PcbLib_RC:RES0402B")
      (description "Resistor 0402 package case")
      (fields
        (field (name "TOLERANCE") "± 1 %")
        (field (name "PART NUMBER") "RC0402FR-07330RL")
        (field (name "PACKAGE") "0402")
      )
      (libsource (lib "Schlib_RC") (part "R0402"))
    )
    (comp (ref "R42")
      (value "330")
      (footprint "PcbLib_RC:RES0402B")
      (description "Resistor 0402 package case")
      (fields
        (field (name "TOLERANCE") "± 1 %")
        (field (name "PART NUMBER") "RC0402FR-07330RL")
        (field (name "PACKAGE") "0402")
      )
      (libsource (lib "Schlib_RC") (part "R0402"))
    )
    (comp (ref "R43")
      (value "330")
      (footprint "PcbLib_RC:RES0402B")
      (description "Resistor 0402 package case")
      (fields
        (field (name "TOLERANCE") "± 1 %")
        (field (name "PART NUMBER") "RC0402FR-07330RL")
        (field (name "PACKAGE") "0402")
      )
      (libsource (lib "Schlib_RC") (part "R0402"))
    )
    (comp (ref "R44")
      (value "330")
      (footprint "PcbLib_RC:RES0402B")
      (description "Resistor 0402 package case")
      (fields
        (field (name "TOLERANCE") "± 1 %")
        (field (name "PART NUMBER") "RC0402FR-07330RL")
        (field (name "PACKAGE") "0402")
      )
      (libsource (lib "Schlib_RC") (part "R0402"))
    )
    (comp (ref "R45")
      (value "330")
      (footprint "PcbLib_RC:RES0402B")
      (description "Resistor 0402 package case")
      (fields
        (field (name "TOLERANCE") "± 1 %")
        (field (name "PART NUMBER") "RC0402FR-07330RL")
        (field (name "PACKAGE") "0402")
      )
      (libsource (lib "Schlib_RC") (part "R0402"))
    )
    (comp (ref "R46")
      (value "330")
      (footprint "PcbLib_RC:RES0402B")
      (description "Resistor 0402 package case")
      (fields
        (field (name "TOLERANCE") "± 1 %")
        (field (name "PART NUMBER") "RC0402FR-07330RL")
        (field (name "PACKAGE") "0402")
      )
      (libsource (lib "Schlib_RC") (part "R0402"))
    )
  )
  (nets
    (net (code "1") (name "/GPIO_ROW0") (class "Default")
      (node (ref "R36") (pin "2") (pinfunction "2_2") (pintype "passive"))
    )
    (net (code "2") (name "/GPIO_ROW1") (class "Default")
      (node (ref "R37") (pin "2") (pinfunction "2_2") (pintype "passive"))
    )
    (net (code "3") (name "/GPIO_ROW2") (class "Default")
      (node (ref "R38") (pin "2") (pinfunction "2_2") (pintype "passive"))
    )
    (net (code "4") (name "/GPIO_ROW3") (class "Default")
      (node (ref "R39") (pin "2") (pinfunction "2_2") (pintype "passive"))
    )
    (net (code "5") (name "/GPIO_ROW4") (class "Default")
      (node (ref "R40") (pin "2") (pinfunction "2_2") (pintype "passive"))
    )
    (net (code "6") (name "/GPIO_ROW5") (class "Default")
      (node (ref "R41") (pin "2") (pinfunction "2_2") (pintype "passive"))
    )
    (net (code "7") (name "/GPIO_ROW6") (class "Default")
      (node (ref "R42") (pin "2") (pinfunction "2_2") (pintype "passive"))
    )
    (net (code "8") (name "/GPIO_ROW7") (class "Default")
      (node (ref "R43") (pin "2") (pinfunction "2_2") (pintype "passive"))
    )
    (net (code "9") (name "/GPIO_ROW8") (class "Default")
      (node (ref "R44") (pin "2") (pinfunction "2_2") (pintype "passive"))
    )
    (net (code "10") (name "/GPIO_ROW9") (class "Default")
      (node (ref "R45") (pin "2") (pinfunction "2_2") (pintype "passive"))
    )
    (net (code "11") (name "/GPIO_ROW10") (class "Default")
      (node (ref "R46") (pin "2") (pinfunction "2_2") (pintype "passive"))
    )
    (net (code "12") (name "/ROW0") (class "Default")
      (node (ref "HL10") (pin "2") (pinfunction "2_2") (pintype "passive"))
      (node (ref "HL11") (pin "2") (pinfunction "2_2") (pintype "passive"))
      (node (ref "HL12") (pin "2") (pinfunction "2_2") (pintype "passive"))
      (node (ref "HL13") (pin "2") (pinfunction "2_2") (pintype "passive"))
      (node (ref "HL14") (pin "2") (pinfunction "2_2") (pintype "passive"))
      (node (ref "HL15") (pin "2") (pinfunction "2_2") (pintype "passive"))
      (node (ref "HL16") (pin "2") (pinfunction "2_2") (pintype "passive"))
      (node (ref "HL17") (pin "2") (pinfunction "2_2") (pintype "passive"))
      (node (ref "HL18") (pin "1") (pinfunction "1_1") (pintype "passive"))
      (node (ref "HL19") (pin "1") (pinfunction "1_1") (pintype "passive"))
      (node (ref "HL20") (pin "1") (pinfunction "1_1") (pintype "passive"))
      (node (ref "HL21") (pin "1") (pinfunction "1_1") (pintype "passive"))
      (node (ref "HL22") (pin "1") (pinfunction "1_1") (pintype "passive"))
      (node (ref "HL23") (pin "1") (pinfunction "1_1") (pintype "passive"))
      (node (ref "HL24") (pin "1") (pinfunction "1_1") (pintype "passive"))
      (node (ref "HL25") (pin "1") (pinfunction "1_1") (pintype "passive"))
      (node (ref "HL26") (pin "1") (pinfunction "1_1") (pintype "passive"))
      (node (ref "HL27") (pin "1") (pinfunction "1_1") (pintype "passive"))
      (node (ref "HL8") (pin "2") (pinfunction "2_2") (pintype "passive"))
      (node (ref "HL9") (pin "2") (pinfunction "2_2") (pintype "passive"))
      (node (ref "R36") (pin "1") (pinfunction "1_1") (pintype "passive"))
    )
    (net (code "13") (name "/ROW1") (class "Default")
      (node (ref "HL18") (pin "2") (pinfunction "2_2") (pintype "passive"))
      (node (ref "HL28") (pin "2") (pinfunction "2_2") (pintype "passive"))
      (node (ref "HL29") (pin "2") (pinfunction "2_2") (pintype "passive"))
      (node (ref "HL30") (pin "2") (pinfunction "2_2") (pintype "passive"))
      (node (ref "HL31") (pin "2") (pinfunction "2_2") (pintype "passive"))
      (node (ref "HL32") (pin "2") (pinfunction "2_2") (pintype "passive"))
      (node (ref "HL33") (pin "2") (pinfunction "2_2") (pintype "passive"))
      (node (ref "HL34") (pin "2") (pinfunction "2_2") (pintype "passive"))
      (node (ref "HL35") (pin "2") (pinfunction "2_2") (pintype "passive"))
      (node (ref "HL36") (pin "2") (pinfunction "2_2") (pintype "passive"))
      (node (ref "HL37") (pin "1") (pinfunction "1_1") (pintype "passive"))
      (node (ref "HL38") (pin "1") (pinfunction "1_1") (pintype "passive"))
      (node (ref "HL39") (pin "1") (pinfunction "1_1") (pintype "passive"))
      (node (ref "HL40") (pin "1") (pinfunction "1_1") (pintype "passive"))
      (node (ref "HL41") (pin "1") (pinfunction "1_1") (pintype "passive"))
      (node (ref "HL42") (pin "1") (pinfunction "1_1") (pintype "passive"))
      (node (ref "HL43") (pin "1") (pinfunction "1_1") (pintype "passive"))
      (node (ref "HL44") (pin "1") (pinfunction "1_1") (pintype "passive"))
      (node (ref "HL45") (pin "1") (pinfunction "1_1") (pintype "passive"))
      (node (ref "HL8") (pin "1") (pinfunction "1_1") (pintype "passive"))
      (node (ref "R37") (pin "1") (pinfunction "1_1") (pintype "passive"))
    )
    (net (code "14") (name "/ROW2") (class "Default")
      (node (ref "HL19") (pin "2") (pinfunction "2_2") (pintype "passive"))
      (node (ref "HL28") (pin "1") (pinfunction "1_1") (pintype "passive"))
      (node (ref "HL37") (pin "2") (pinfunction "2_2") (pintype "passive"))
      (node (ref "HL46") (pin "2") (pinfunction "2_2") (pintype "passive"))
      (node (ref "HL47") (pin "2") (pinfunction "2_2") (pintype "passive"))
      (node (ref "HL48") (pin "2") (pinfunction "2_2") (pintype "passive"))
      (node (ref "HL49") (pin "2") (pinfunction "2_2") (pintype "passive"))
      (node (ref "HL50") (pin "2") (pinfunction "2_2") (pintype "passive"))
      (node (ref "HL51") (pin "2") (pinfunction "2_2") (pintype "passive"))
      (node (ref "HL52") (pin "2") (pinfunction "2_2") (pintype "passive"))
      (node (ref "HL53") (pin "2") (pinfunction "2_2") (pintype "passive"))
      (node (ref "HL54") (pin "1") (pinfunction "1_1") (pintype "passive"))
      (node (ref "HL55") (pin "1") (pinfunction "1_1") (pintype "passive"))
      (node (ref "HL56") (pin "1") (pinfunction "1_1") (pintype "passive"))
      (node (ref "HL57") (pin "1") (pinfunction "1_1") (pintype "passive"))
      (node (ref "HL58") (pin "1") (pinfunction "1_1") (pintype "passive"))
      (node (ref "HL59") (pin "1") (pinfunction "1_1") (pintype "passive"))
      (node (ref "HL60") (pin "1") (pinfunction "1_1") (pintype "passive"))
      (node (ref "HL61") (pin "1") (pinfunction "1_1") (pintype "passive"))
      (node (ref "HL9") (pin "1") (pinfunction "1_1") (pintype "passive"))
      (node (ref "R38") (pin "1") (pinfunction "1_1") (pintype "passive"))
    )
    (net (code "15") (name "/ROW3") (class "Default")
      (node (ref "HL10") (pin "1") (pinfunction "1_1") (pintype "passive"))
      (node (ref "HL20") (pin "2") (pinfunction "2_2") (pintype "passive"))
      (node (ref "HL29") (pin "1") (pinfunction "1_1") (pintype "passive"))
      (node (ref "HL38") (pin "2") (pinfunction "2_2") (pintype "passive"))
      (node (ref "HL46") (pin "1") (pinfunction "1_1") (pintype "passive"))
      (node (ref "HL54") (pin "2") (pinfunction "2_2") (pintype "passive"))
      (node (ref "HL62") (pin "2") (pinfunction "2_2") (pintype "passive"))
      (node (ref "HL63") (pin "2") (pinfunction "2_2") (pintype "passive"))
      (node (ref "HL64") (pin "2") (pinfunction "2_2") (pintype "passive"))
      (node (ref "HL65") (pin "2") (pinfunction "2_2") (pintype "passive"))
      (node (ref "HL66") (pin "2") (pinfunction "2_2") (pintype "passive"))
      (node (ref "HL67") (pin "2") (pinfunction "2_2") (pintype "passive"))
      (node (ref "HL68") (pin "1") (pinfunction "1_1") (pintype "passive"))
      (node (ref "HL69") (pin "1") (pinfunction "1_1") (pintype "passive"))
      (node (ref "HL70") (pin "1") (pinfunction "1_1") (pintype "passive"))
      (node (ref "HL71") (pin "1") (pinfunction "1_1") (pintype "passive"))
      (node (ref "HL72") (pin "1") (pinfunction "1_1") (pintype "passive"))
      (node (ref "HL73") (pin "1") (pinfunction "1_1") (pintype "passive"))
      (node (ref "R39") (pin "1") (pinfunction "1_1") (pintype "passive"))
    )
    (net (code "16") (name "/ROW4") (class "Default")
      (node (ref "HL11") (pin "1") (pinfunction "1_1") (pintype "passive"))
      (node (ref "HL21") (pin "2") (pinfunction "2_2") (pintype "passive"))
      (node (ref "HL30") (pin "1") (pinfunction "1_1") (pintype "passive"))
      (node (ref "HL39") (pin "2") (pinfunction "2_2") (pintype "passive"))
      (node (ref "HL47") (pin "1") (pinfunction "1_1") (pintype "passive"))
      (node (ref "HL55") (pin "2") (pinfunction "2_2") (pintype "passive"))
      (node (ref "HL62") (pin "1") (pinfunction "1_1") (pintype "passive"))
      (node (ref "HL68") (pin "2") (pinfunction "2_2") (pintype "passive"))
      (node (ref "HL74") (pin "2") (pinfunction "2_2") (pintype "passive"))
      (node (ref "HL75") (pin "2") (pinfunction "2_2") (pintype "passive"))
      (node (ref "HL76") (pin "2") (pinfunction "2_2") (pintype "passive"))
      (node (ref "HL77") (pin "2") (pinfunction "2_2") (pintype "passive"))
      (node (ref "HL78") (pin "2") (pinfunction "2_2") (pintype "passive"))
      (node (ref "HL79") (pin "1") (pinfunction "1_1") (pintype "passive"))
      (node (ref "HL80") (pin "1") (pinfunction "1_1") (pintype "passive"))
      (node (ref "HL81") (pin "1") (pinfunction "1_1") (pintype "passive"))
      (node (ref "HL82") (pin "1") (pinfunction "1_1") (pintype "passive"))
      (node (ref "HL83") (pin "1") (pinfunction "1_1") (pintype "passive"))
      (node (ref "R40") (pin "1") (pinfunction "1_1") (pintype "passive"))
    )
    (net (code "17") (name "/ROW5") (class "Default")
      (node (ref "HL12") (pin "1") (pinfunction "1_1") (pintype "passive"))
      (node (ref "HL22") (pin "2") (pinfunction "2_2") (pintype "passive"))
      (node (ref "HL31") (pin "1") (pinfunction "1_1") (pintype "passive"))
      (node (ref "HL40") (pin "2") (pinfunction "2_2") (pintype "passive"))
      (node (ref "HL48") (pin "1") (pinfunction "1_1") (pintype "passive"))
      (node (ref "HL56") (pin "2") (pinfunction "2_2") (pintype "passive"))
      (node (ref "HL63") (pin "1") (pinfunction "1_1") (pintype "passive"))
      (node (ref "HL69") (pin "2") (pinfunction "2_2") (pintype "passive"))
      (node (ref "HL74") (pin "1") (pinfunction "1_1") (pintype "passive"))
      (node (ref "HL79") (pin "2") (pinfunction "2_2") (pintype "passive"))
      (node (ref "HL84") (pin "2") (pinfunction "2_2") (pintype "passive"))
      (node (ref "HL85") (pin "2") (pinfunction "2_2") (pintype "passive"))
      (node (ref "HL86") (pin "2") (pinfunction "2_2") (pintype "passive"))
      (node (ref "HL87") (pin "2") (pinfunction "2_2") (pintype "passive"))
      (node (ref "HL88") (pin "1") (pinfunction "1_1") (pintype "passive"))
      (node (ref "HL89") (pin "1") (pinfunction "1_1") (pintype "passive"))
      (node (ref "HL90") (pin "1") (pinfunction "1_1") (pintype "passive"))
      (node (ref "HL91") (pin "1") (pinfunction "1_1") (pintype "passive"))
      (node (ref "R41") (pin "1") (pinfunction "1_1") (pintype "passive"))
    )
    (net (code "18") (name "/ROW6") (class "Default")
      (node (ref "HL13") (pin "1") (pinfunction "1_1") (pintype "passive"))
      (node (ref "HL23") (pin "2") (pinfunction "2_2") (pintype "passive"))
      (node (ref "HL32") (pin "1") (pinfunction "1_1") (pintype "passive"))
      (node (ref "HL41") (pin "2") (pinfunction "2_2") (pintype "passive"))
      (node (ref "HL49") (pin "1") (pinfunction "1_1") (pintype "passive"))
      (node (ref "HL57") (pin "2") (pinfunction "2_2") (pintype "passive"))
      (node (ref "HL64") (pin "1") (pinfunction "1_1") (pintype "passive"))
      (node (ref "HL70") (pin "2") (pinfunction "2_2") (pintype "passive"))
      (node (ref "HL75") (pin "1") (pinfunction "1_1") (pintype "passive"))
      (node (ref "HL80") (pin "2") (pinfunction "2_2") (pintype "passive"))
      (node (ref "HL84") (pin "1") (pinfunction "1_1") (pintype "passive"))
      (node (ref "HL88") (pin "2") (pinfunction "2_2") (pintype "passive"))
      (node (ref "HL92") (pin "2") (pinfunction "2_2") (pintype "passive"))
      (node (ref "HL93") (pin "2") (pinfunction "2_2") (pintype "passive"))
      (node (ref "HL94") (pin "2") (pinfunction "2_2") (pintype "passive"))
      (node (ref "HL95") (pin "1") (pinfunction "1_1") (pintype "passive"))
      (node (ref "HL96") (pin "1") (pinfunction "1_1") (pintype "passive"))
      (node (ref "HL97") (pin "1") (pinfunction "1_1") (pintype "passive"))
      (node (ref "R42") (pin "1") (pinfunction "1_1") (pintype "passive"))
    )
    (net (code "19") (name "/ROW7") (class "Default")
      (node (ref "HL100") (pin "1") (pinfunction "1_1") (pintype "passive"))
      (node (ref "HL101") (pin "1") (pinfunction "1_1") (pintype "passive"))
      (node (ref "HL14") (pin "1") (pinfunction "1_1") (pintype "passive"))
      (node (ref "HL24") (pin "2") (pinfunction "2_2") (pintype "passive"))
      (node (ref "HL33") (pin "1") (pinfunction "1_1") (pintype "passive"))
      (node (ref "HL42") (pin "2") (pinfunction "2_2") (pintype "passive"))
      (node (ref "HL50") (pin "1") (pinfunction "1_1") (pintype "passive"))
      (node (ref "HL58") (pin "2") (pinfunction "2_2") (pintype "passive"))
      (node (ref "HL65") (pin "1") (pinfunction "1_1") (pintype "passive"))
      (node (ref "HL71") (pin "2") (pinfunction "2_2") (pintype "passive"))
      (node (ref "HL76") (pin "1") (pinfunction "1_1") (pintype "passive"))
      (node (ref "HL81") (pin "2") (pinfunction "2_2") (pintype "passive"))
      (node (ref "HL85") (pin "1") (pinfunction "1_1") (pintype "passive"))
      (node (ref "HL89") (pin "2") (pinfunction "2_2") (pintype "passive"))
      (node (ref "HL92") (pin "1") (pinfunction "1_1") (pintype "passive"))
      (node (ref "HL95") (pin "2") (pinfunction "2_2") (pintype "passive"))
      (node (ref "HL98") (pin "2") (pinfunction "2_2") (pintype "passive"))
      (node (ref "HL99") (pin "2") (pinfunction "2_2") (pintype "passive"))
      (node (ref "R43") (pin "1") (pinfunction "1_1") (pintype "passive"))
    )
    (net (code "20") (name "/ROW8") (class "Default")
      (node (ref "HL100") (pin "2") (pinfunction "2_2") (pintype "passive"))
      (node (ref "HL102") (pin "2") (pinfunction "2_2") (pintype "passive"))
      (node (ref "HL103") (pin "1") (pinfunction "1_1") (pintype "passive"))
      (node (ref "HL15") (pin "1") (pinfunction "1_1") (pintype "passive"))
      (node (ref "HL25") (pin "2") (pinfunction "2_2") (pintype "passive"))
      (node (ref "HL34") (pin "1") (pinfunction "1_1") (pintype "passive"))
      (node (ref "HL43") (pin "2") (pinfunction "2_2") (pintype "passive"))
      (node (ref "HL51") (pin "1") (pinfunction "1_1") (pintype "passive"))
      (node (ref "HL59") (pin "2") (pinfunction "2_2") (pintype "passive"))
      (node (ref "HL66") (pin "1") (pinfunction "1_1") (pintype "passive"))
      (node (ref "HL72") (pin "2") (pinfunction "2_2") (pintype "passive"))
      (node (ref "HL77") (pin "1") (pinfunction "1_1") (pintype "passive"))
      (node (ref "HL82") (pin "2") (pinfunction "2_2") (pintype "passive"))
      (node (ref "HL86") (pin "1") (pinfunction "1_1") (pintype "passive"))
      (node (ref "HL90") (pin "2") (pinfunction "2_2") (pintype "passive"))
      (node (ref "HL93") (pin "1") (pinfunction "1_1") (pintype "passive"))
      (node (ref "HL96") (pin "2") (pinfunction "2_2") (pintype "passive"))
      (node (ref "HL98") (pin "1") (pinfunction "1_1") (pintype "passive"))
      (node (ref "R44") (pin "1") (pinfunction "1_1") (pintype "passive"))
    )
    (net (code "21") (name "/ROW9") (class "Default")
      (node (ref "HL101") (pin "2") (pinfunction "2_2") (pintype "passive"))
      (node (ref "HL102") (pin "1") (pinfunction "1_1") (pintype "passive"))
      (node (ref "HL103") (pin "2") (pinfunction "2_2") (pintype "passive"))
      (node (ref "HL16") (pin "1") (pinfunction "1_1") (pintype "passive"))
      (node (ref "HL26") (pin "2") (pinfunction "2_2") (pintype "passive"))
      (node (ref "HL35") (pin "1") (pinfunction "1_1") (pintype "passive"))
      (node (ref "HL44") (pin "2") (pinfunction "2_2") (pintype "passive"))
      (node (ref "HL52") (pin "1") (pinfunction "1_1") (pintype "passive"))
      (node (ref "HL60") (pin "2") (pinfunction "2_2") (pintype "passive"))
      (node (ref "HL67") (pin "1") (pinfunction "1_1") (pintype "passive"))
      (node (ref "HL73") (pin "2") (pinfunction "2_2") (pintype "passive"))
      (node (ref "HL78") (pin "1") (pinfunction "1_1") (pintype "passive"))
      (node (ref "HL83") (pin "2") (pinfunction "2_2") (pintype "passive"))
      (node (ref "HL87") (pin "1") (pinfunction "1_1") (pintype "passive"))
      (node (ref "HL91") (pin "2") (pinfunction "2_2") (pintype "passive"))
      (node (ref "HL94") (pin "1") (pinfunction "1_1") (pintype "passive"))
      (node (ref "HL97") (pin "2") (pinfunction "2_2") (pintype "passive"))
      (node (ref "HL99") (pin "1") (pinfunction "1_1") (pintype "passive"))
      (node (ref "R45") (pin "1") (pinfunction "1_1") (pintype "passive"))
    )
    (net (code "22") (name "/ROW10") (class "Default")
      (node (ref "HL17") (pin "1") (pinfunction "1_1") (pintype "passive"))
      (node (ref "HL27") (pin "2") (pinfunction "2_2") (pintype "passive"))
      (node (ref "HL36") (pin "1") (pinfunction "1_1") (pintype "passive"))
      (node (ref "HL45") (pin "2") (pinfunction "2_2") (pintype "passive"))
      (node (ref "HL53") (pin "1") (pinfunction "1_1") (pintype "passive"))
      (node (ref "HL61") (pin "2") (pinfunction "2_2") (pintype "passive"))
      (node (ref "R46") (pin "1") (pinfunction "1_1") (pintype "passive"))
    )
  )
)
